# gas-sensor-mics-6814-mk-1_0.net
KiCad netlist of a schematic drawn in EAGLE
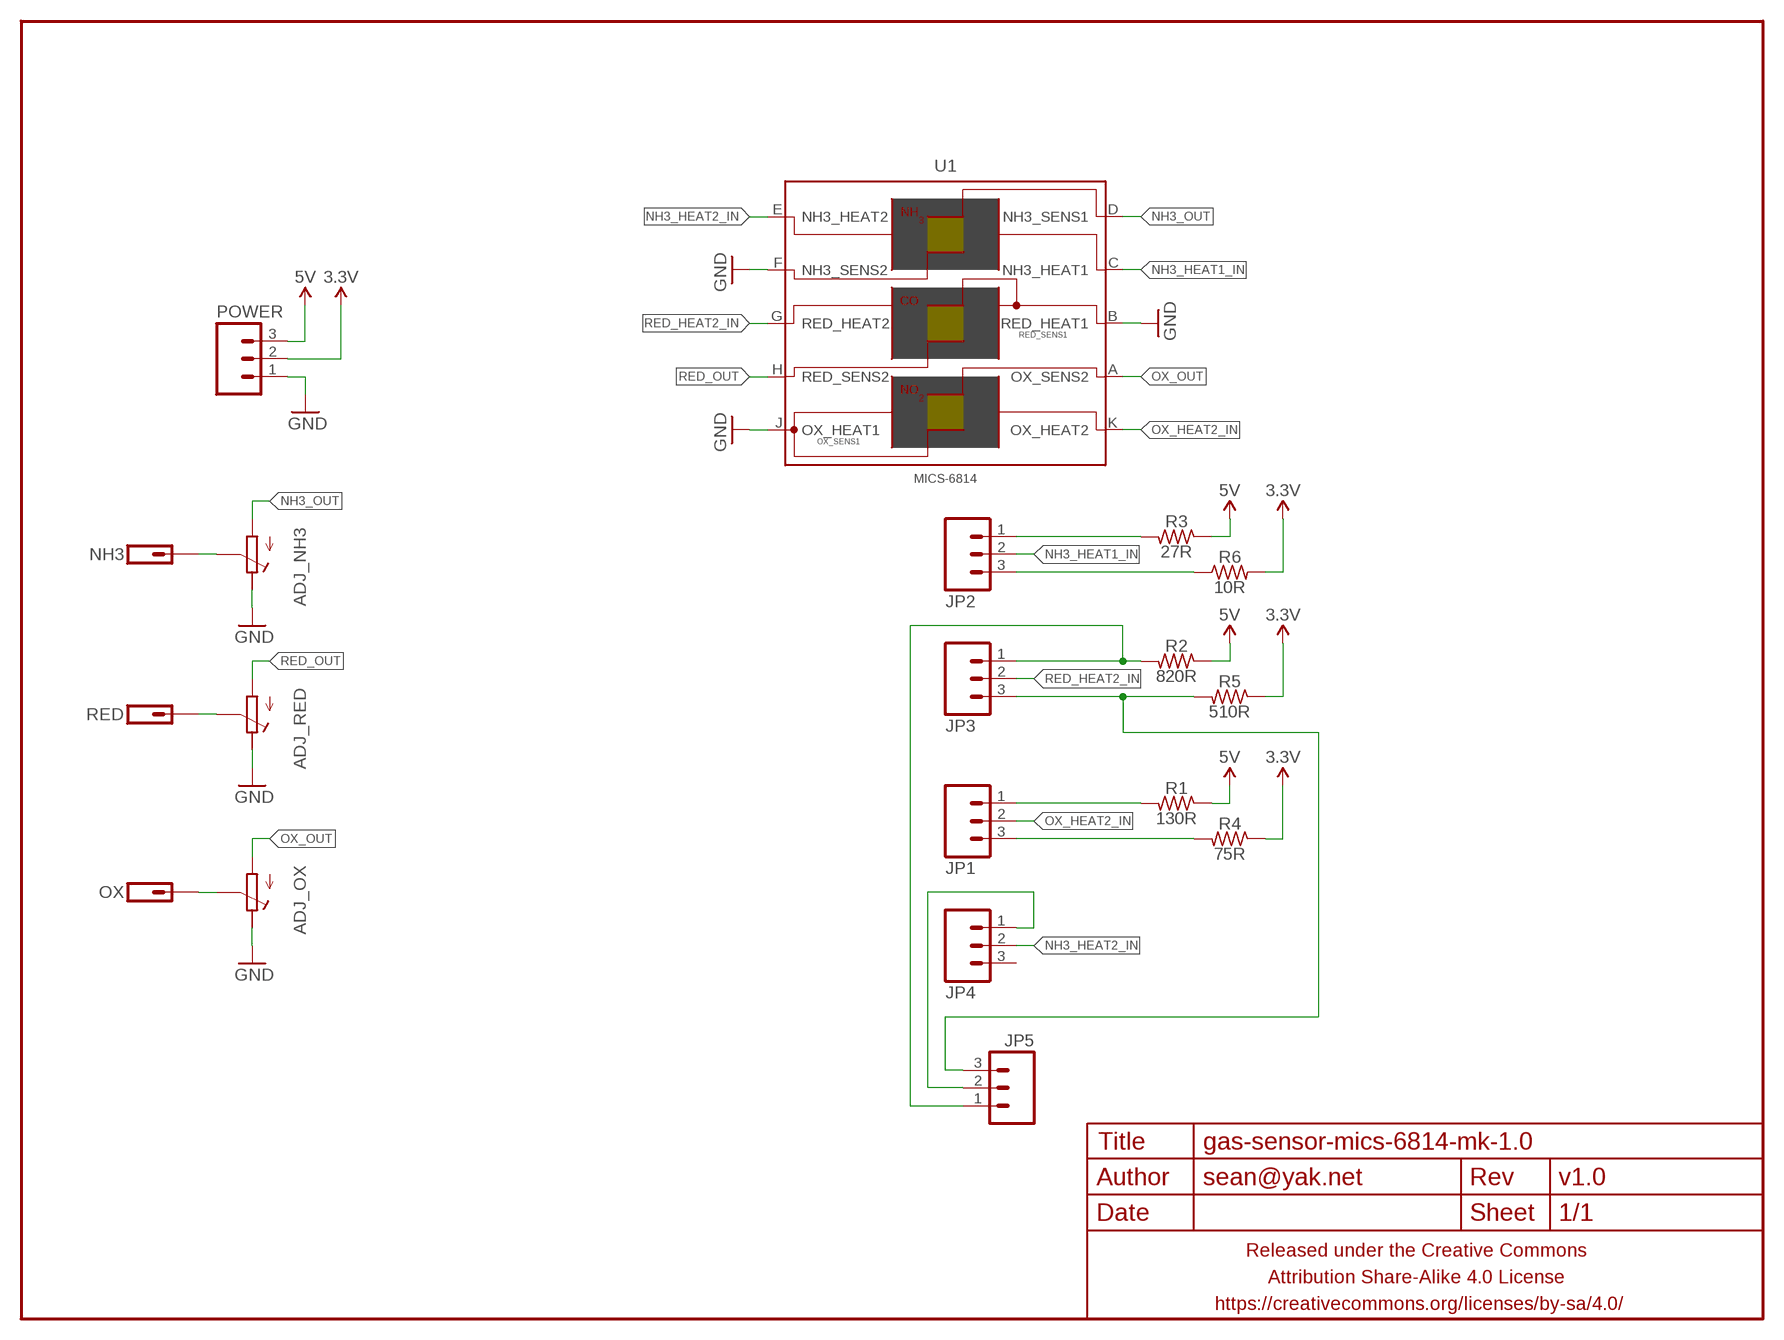
[diagram p0: schematic, sheet 1]

(export (version "E")
  (design (tool "Eeschema 10.0.6"))
  (components
    (comp (ref "ADJ_NH3")
      (value "POTENTIOMETEREVM3Y")
      (footprint "eagle-import:EVM3Y")
      (libsource (lib "eagle-import") (part "POTENTIOMETEREVM3Y"))
    )
    (comp (ref "ADJ_OX")
      (value "POTENTIOMETEREVM3Y")
      (footprint "eagle-import:EVM3Y")
      (libsource (lib "eagle-import") (part "POTENTIOMETEREVM3Y"))
    )
    (comp (ref "ADJ_RED")
      (value "POTENTIOMETEREVM3Y")
      (footprint "eagle-import:EVM3Y")
      (libsource (lib "eagle-import") (part "POTENTIOMETEREVM3Y"))
    )
    (comp (ref "FRAME1")
      (value "FRAME-LETTERNO_PACKAGE")
      (footprint "eagle-import:DUMMY")
      (fields (field (name "DESIGNER") "sean@yak.net") (field (name "VERSION") "v1.0"))
      (libsource (lib "eagle-import") (part "FRAME-LETTERNO_PACKAGE"))
    )
    (comp (ref "JP1")
      (value "M03PTH-CENTERED")
      (footprint "eagle-import:1X03-CENTERED")
      (libsource (lib "eagle-import") (part "M03PTH-CENTERED"))
    )
    (comp (ref "JP2")
      (value "M03PTH-CENTERED")
      (footprint "eagle-import:1X03-CENTERED")
      (libsource (lib "eagle-import") (part "M03PTH-CENTERED"))
    )
    (comp (ref "JP3")
      (value "M03PTH-CENTERED")
      (footprint "eagle-import:1X03-CENTERED")
      (libsource (lib "eagle-import") (part "M03PTH-CENTERED"))
    )
    (comp (ref "JP4")
      (value "M03PTH-CENTERED")
      (footprint "eagle-import:1X03-CENTERED")
      (libsource (lib "eagle-import") (part "M03PTH-CENTERED"))
    )
    (comp (ref "JP5")
      (value "M03PTH-CENTERED")
      (footprint "eagle-import:1X03-CENTERED")
      (libsource (lib "eagle-import") (part "M03PTH-CENTERED"))
    )
    (comp (ref "NH3")
      (value "M01PTH-2MM-OFFSET")
      (footprint "eagle-import:1X01_2MM_OFFSET")
      (libsource (lib "eagle-import") (part "M01PTH-2MM-OFFSET"))
    )
    (comp (ref "OX")
      (value "M01PTH-2MM-OFFSET")
      (footprint "eagle-import:1X01_2MM_OFFSET")
      (libsource (lib "eagle-import") (part "M01PTH-2MM-OFFSET"))
    )
    (comp (ref "POWER")
      (value "M03PTH-CENTERED")
      (footprint "eagle-import:1X03-CENTERED")
      (libsource (lib "eagle-import") (part "M03PTH-CENTERED"))
    )
    (comp (ref "R1")
      (value "130R")
      (footprint "eagle-import:R0603-TIGHTER")
      (libsource (lib "eagle-import") (part "RESISTORR0603-TIGHTER"))
    )
    (comp (ref "R2")
      (value "820R")
      (footprint "eagle-import:R0603-TIGHTER")
      (libsource (lib "eagle-import") (part "RESISTORR0603-TIGHTER"))
    )
    (comp (ref "R3")
      (value "27R")
      (footprint "eagle-import:R0603-TIGHTER")
      (libsource (lib "eagle-import") (part "RESISTORR0603-TIGHTER"))
    )
    (comp (ref "R4")
      (value "75R")
      (footprint "eagle-import:R0603-TIGHTER")
      (libsource (lib "eagle-import") (part "RESISTORR0603-TIGHTER"))
    )
    (comp (ref "R5")
      (value "510R")
      (footprint "eagle-import:R0603-TIGHTER")
      (libsource (lib "eagle-import") (part "RESISTORR0603-TIGHTER"))
    )
    (comp (ref "R6")
      (value "10R")
      (footprint "eagle-import:R0603-TIGHTER")
      (libsource (lib "eagle-import") (part "RESISTORR0603-TIGHTER"))
    )
    (comp (ref "RED")
      (value "M01PTH-2MM-OFFSET")
      (footprint "eagle-import:1X01_2MM_OFFSET")
      (libsource (lib "eagle-import") (part "M01PTH-2MM-OFFSET"))
    )
    (comp (ref "U1")
      (value "MICS-6814")
      (footprint "eagle-import:MICS-10-PIN")
      (libsource (lib "eagle-import") (part "MICS-6814"))
    )
  )
  (nets
    (net (code "1") (name "3.3V") (class "Default")
      (node (ref "POWER") (pin "2") (pinfunction "2_2") (pintype "passive"))
      (node (ref "R4") (pin "1") (pinfunction "1_1") (pintype "passive"))
      (node (ref "R5") (pin "1") (pinfunction "1_1") (pintype "passive"))
      (node (ref "R6") (pin "2") (pinfunction "2_2") (pintype "passive"))
    )
    (net (code "2") (name "5V") (class "Default")
      (node (ref "POWER") (pin "3") (pinfunction "3_3") (pintype "passive"))
      (node (ref "R1") (pin "1") (pinfunction "1_1") (pintype "passive"))
      (node (ref "R2") (pin "1") (pinfunction "1_1") (pintype "passive"))
      (node (ref "R3") (pin "1") (pinfunction "1_1") (pintype "passive"))
    )
    (net (code "3") (name "GND") (class "Default")
      (node (ref "ADJ_NH3") (pin "E") (pinfunction "E_E") (pintype "passive"))
      (node (ref "ADJ_OX") (pin "E") (pinfunction "E_E") (pintype "passive"))
      (node (ref "ADJ_RED") (pin "E") (pinfunction "E_E") (pintype "passive"))
      (node (ref "POWER") (pin "1") (pinfunction "1_1") (pintype "passive"))
      (node (ref "U1") (pin "B") (pinfunction "RED_HEAT1_B") (pintype "bidirectional"))
      (node (ref "U1") (pin "F") (pinfunction "NH3_SENS2_F") (pintype "bidirectional"))
      (node (ref "U1") (pin "J") (pinfunction "OX_HEAT1_J") (pintype "bidirectional"))
    )
    (net (code "4") (name "NH3_HEAT1_IN") (class "Default")
      (node (ref "JP2") (pin "2") (pinfunction "2_2") (pintype "passive"))
      (node (ref "U1") (pin "C") (pinfunction "NH3_HEAT1_C") (pintype "bidirectional"))
    )
    (net (code "5") (name "NH3_HEAT2_IN") (class "Default")
      (node (ref "JP4") (pin "2") (pinfunction "2_2") (pintype "passive"))
      (node (ref "U1") (pin "E") (pinfunction "NH3_HEAT2_E") (pintype "bidirectional"))
    )
    (net (code "6") (name "NH3_OUT") (class "Default")
      (node (ref "ADJ_NH3") (pin "A") (pinfunction "A_A") (pintype "passive"))
      (node (ref "U1") (pin "D") (pinfunction "NH3_SENS1_D") (pintype "bidirectional"))
    )
    (net (code "7") (name "Net-(ADJ_NH3-PadS)") (class "Default")
      (node (ref "ADJ_NH3") (pin "S") (pinfunction "S_S") (pintype "passive"))
      (node (ref "NH3") (pin "1") (pinfunction "1_1") (pintype "passive"))
    )
    (net (code "8") (name "Net-(ADJ_OX-PadS)") (class "Default")
      (node (ref "ADJ_OX") (pin "S") (pinfunction "S_S") (pintype "passive"))
      (node (ref "OX") (pin "1") (pinfunction "1_1") (pintype "passive"))
    )
    (net (code "9") (name "Net-(ADJ_RED-PadS)") (class "Default")
      (node (ref "ADJ_RED") (pin "S") (pinfunction "S_S") (pintype "passive"))
      (node (ref "RED") (pin "1") (pinfunction "1_1") (pintype "passive"))
    )
    (net (code "10") (name "Net-(JP1-Pad1)") (class "Default")
      (node (ref "JP1") (pin "1") (pinfunction "1_1") (pintype "passive"))
      (node (ref "R1") (pin "2") (pinfunction "2_2") (pintype "passive"))
    )
    (net (code "11") (name "Net-(JP1-Pad3)") (class "Default")
      (node (ref "JP1") (pin "3") (pinfunction "3_3") (pintype "passive"))
      (node (ref "R4") (pin "2") (pinfunction "2_2") (pintype "passive"))
    )
    (net (code "12") (name "Net-(JP2-Pad1)") (class "Default")
      (node (ref "JP2") (pin "1") (pinfunction "1_1") (pintype "passive"))
      (node (ref "R3") (pin "2") (pinfunction "2_2") (pintype "passive"))
    )
    (net (code "13") (name "Net-(JP2-Pad3)") (class "Default")
      (node (ref "JP2") (pin "3") (pinfunction "3_3") (pintype "passive"))
      (node (ref "R6") (pin "1") (pinfunction "1_1") (pintype "passive"))
    )
    (net (code "14") (name "Net-(JP3-Pad1)") (class "Default")
      (node (ref "JP3") (pin "1") (pinfunction "1_1") (pintype "passive"))
      (node (ref "JP5") (pin "1") (pinfunction "1_1") (pintype "passive"))
      (node (ref "R2") (pin "2") (pinfunction "2_2") (pintype "passive"))
    )
    (net (code "15") (name "Net-(JP3-Pad3)") (class "Default")
      (node (ref "JP3") (pin "3") (pinfunction "3_3") (pintype "passive"))
      (node (ref "JP5") (pin "3") (pinfunction "3_3") (pintype "passive"))
      (node (ref "R5") (pin "2") (pinfunction "2_2") (pintype "passive"))
    )
    (net (code "16") (name "Net-(JP4-Pad1)") (class "Default")
      (node (ref "JP4") (pin "1") (pinfunction "1_1") (pintype "passive"))
      (node (ref "JP5") (pin "2") (pinfunction "2_2") (pintype "passive"))
    )
    (net (code "17") (name "OX_HEAT2_IN") (class "Default")
      (node (ref "JP1") (pin "2") (pinfunction "2_2") (pintype "passive"))
      (node (ref "U1") (pin "K") (pinfunction "OX_HEAT2_K") (pintype "bidirectional"))
    )
    (net (code "18") (name "OX_OUT") (class "Default")
      (node (ref "ADJ_OX") (pin "A") (pinfunction "A_A") (pintype "passive"))
      (node (ref "U1") (pin "A") (pinfunction "OX_SENS2_A") (pintype "bidirectional"))
    )
    (net (code "19") (name "RED_HEAT2_IN") (class "Default")
      (node (ref "JP3") (pin "2") (pinfunction "2_2") (pintype "passive"))
      (node (ref "U1") (pin "G") (pinfunction "RED_HEAT2_G") (pintype "bidirectional"))
    )
    (net (code "20") (name "RED_OUT") (class "Default")
      (node (ref "ADJ_RED") (pin "A") (pinfunction "A_A") (pintype "passive"))
      (node (ref "U1") (pin "H") (pinfunction "RED_SENS2_H") (pintype "bidirectional"))
    )
    (net (code "21") (name "unconnected-(JP4-Pad3)") (class "Default")
      (node (ref "JP4") (pin "3") (pinfunction "3_3") (pintype "passive"))
    )
  )
)
